# RAM_SDR_BGA54.net
KiCad netlist of a schematic drawn in Altium Designer
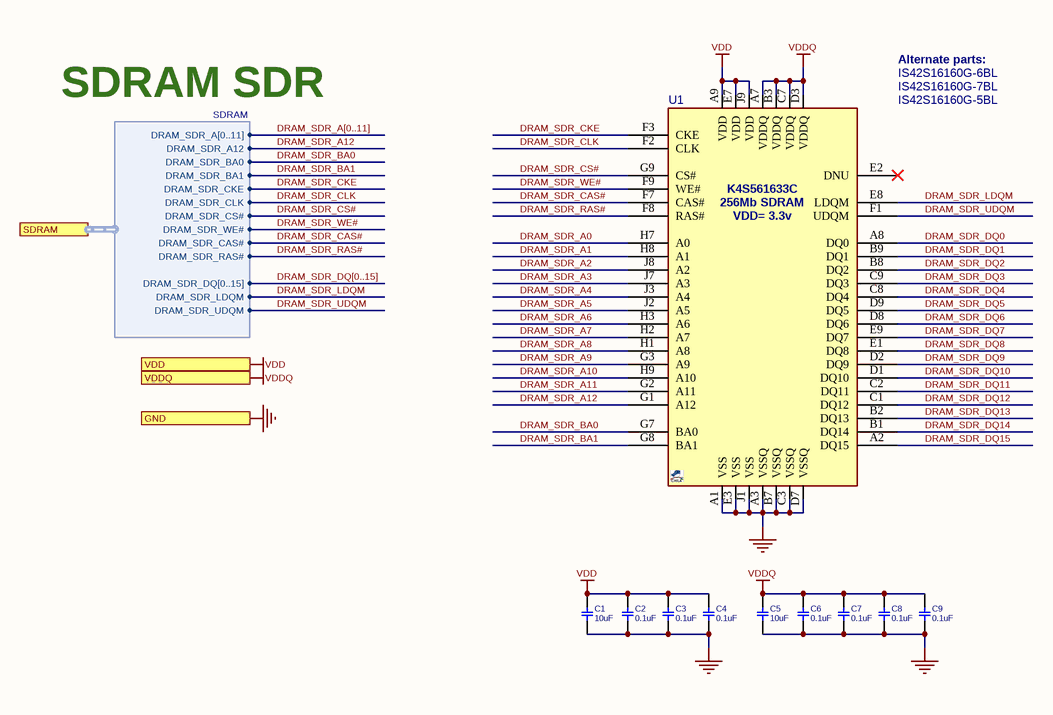
[diagram p0: RAM_SDR_BGA54.SchDoc]

(export (version "E")
  (design (tool "Eeschema 10.0.6"))
  (components
    (comp (ref "C1")
      (value "10uF")
      (footprint "C0402A")
      (description "CAP, MLCC")
      (fields (field (name "MANF_P#") "CL05A106MP5NUNC") (field (name "MANF") "Samsung"))
      (libsource (lib "passive_smd") (part "CAP_SMD_MLCC"))
    )
    (comp (ref "C2")
      (value "0.1uF")
      (footprint "C0402A")
      (description "CAP, MLCC")
      (fields (field (name "MANF_P#") "GRM155R61E104") (field (name "MANF") "Murata"))
      (libsource (lib "passive_smd") (part "CAP_SMD_MLCC"))
    )
    (comp (ref "C3")
      (value "0.1uF")
      (footprint "C0402A")
      (description "CAP, MLCC")
      (fields (field (name "MANF_P#") "GRM155R61E104") (field (name "MANF") "Murata"))
      (libsource (lib "passive_smd") (part "CAP_SMD_MLCC"))
    )
    (comp (ref "C4")
      (value "0.1uF")
      (footprint "C0402A")
      (description "CAP, MLCC")
      (fields (field (name "MANF_P#") "GRM155R61E104") (field (name "MANF") "Murata"))
      (libsource (lib "passive_smd") (part "CAP_SMD_MLCC"))
    )
    (comp (ref "C5")
      (value "10uF")
      (footprint "C0402A")
      (description "CAP, MLCC")
      (fields (field (name "MANF_P#") "CL05A106MP5NUNC") (field (name "MANF") "Samsung"))
      (libsource (lib "passive_smd") (part "CAP_SMD_MLCC"))
    )
    (comp (ref "C6")
      (value "0.1uF")
      (footprint "C0402A")
      (description "CAP, MLCC")
      (fields (field (name "MANF_P#") "GRM155R61E104") (field (name "MANF") "Murata"))
      (libsource (lib "passive_smd") (part "CAP_SMD_MLCC"))
    )
    (comp (ref "C7")
      (value "0.1uF")
      (footprint "C0402A")
      (description "CAP, MLCC")
      (fields (field (name "MANF_P#") "GRM155R61E104") (field (name "MANF") "Murata"))
      (libsource (lib "passive_smd") (part "CAP_SMD_MLCC"))
    )
    (comp (ref "C8")
      (value "0.1uF")
      (footprint "C0402A")
      (description "CAP, MLCC")
      (fields (field (name "MANF_P#") "GRM155R61E104") (field (name "MANF") "Murata"))
      (libsource (lib "passive_smd") (part "CAP_SMD_MLCC"))
    )
    (comp (ref "C9")
      (value "0.1uF")
      (footprint "C0402A")
      (description "CAP, MLCC")
      (fields (field (name "MANF_P#") "GRM155R61E104") (field (name "MANF") "Murata"))
      (libsource (lib "passive_smd") (part "CAP_SMD_MLCC"))
    )
    (comp (ref "U1")
      (value "K4S561633C")
      (footprint "BGA80_54_8X8")
      (description "SDRAM, 256Mb(4MbX16bX4), BGA-54")
      (fields (field (name "MANF") "ISSI") (field (name "MANF_P#") "K4S561633C-RL75"))
      (libsource (lib "memory_sdram") (part "SDRAM_K4S561633C_BGA54"))
    )
  )
  (nets
    (net (code "2") (name "/DRAM_SDR_A0") (class "Default")
      (node (ref "U1") (pin "H7") (pinfunction "A0_H7") (pintype "passive"))
    )
    (net (code "3") (name "/DRAM_SDR_A1") (class "Default")
      (node (ref "U1") (pin "H8") (pinfunction "A1_H8") (pintype "passive"))
    )
    (net (code "4") (name "/DRAM_SDR_A2") (class "Default")
      (node (ref "U1") (pin "J8") (pinfunction "A2_J8") (pintype "passive"))
    )
    (net (code "5") (name "/DRAM_SDR_A3") (class "Default")
      (node (ref "U1") (pin "J7") (pinfunction "A3_J7") (pintype "passive"))
    )
    (net (code "6") (name "/DRAM_SDR_A4") (class "Default")
      (node (ref "U1") (pin "J3") (pinfunction "A4_J3") (pintype "passive"))
    )
    (net (code "7") (name "/DRAM_SDR_A5") (class "Default")
      (node (ref "U1") (pin "J2") (pinfunction "A5_J2") (pintype "passive"))
    )
    (net (code "8") (name "/DRAM_SDR_A6") (class "Default")
      (node (ref "U1") (pin "H3") (pinfunction "A6_H3") (pintype "passive"))
    )
    (net (code "9") (name "/DRAM_SDR_A7") (class "Default")
      (node (ref "U1") (pin "H2") (pinfunction "A7_H2") (pintype "passive"))
    )
    (net (code "10") (name "/DRAM_SDR_A8") (class "Default")
      (node (ref "U1") (pin "H1") (pinfunction "A8_H1") (pintype "passive"))
    )
    (net (code "11") (name "/DRAM_SDR_A9") (class "Default")
      (node (ref "U1") (pin "G3") (pinfunction "A9_G3") (pintype "passive"))
    )
    (net (code "12") (name "/DRAM_SDR_A10") (class "Default")
      (node (ref "U1") (pin "H9") (pinfunction "A10_H9") (pintype "passive"))
    )
    (net (code "13") (name "/DRAM_SDR_A11") (class "Default")
      (node (ref "U1") (pin "G2") (pinfunction "A11_G2") (pintype "passive"))
    )
    (net (code "14") (name "/DRAM_SDR_A12") (class "Default")
      (node (ref "U1") (pin "G1") (pinfunction "A12_G1") (pintype "passive"))
    )
    (net (code "16") (name "/DRAM_SDR_BA0") (class "Default")
      (node (ref "U1") (pin "G7") (pinfunction "BA0_G7") (pintype "passive"))
    )
    (net (code "17") (name "/DRAM_SDR_BA1") (class "Default")
      (node (ref "U1") (pin "G8") (pinfunction "BA1_G8") (pintype "passive"))
    )
    (net (code "18") (name "/DRAM_SDR_CAS#") (class "Default")
      (node (ref "U1") (pin "F7") (pinfunction "CAS#_F7") (pintype "passive"))
    )
    (net (code "19") (name "/DRAM_SDR_CKE") (class "Default")
      (node (ref "U1") (pin "F3") (pinfunction "CKE_F3") (pintype "passive"))
    )
    (net (code "20") (name "/DRAM_SDR_CLK") (class "Default")
      (node (ref "U1") (pin "F2") (pinfunction "CLK_F2") (pintype "passive"))
    )
    (net (code "21") (name "/DRAM_SDR_CS#") (class "Default")
      (node (ref "U1") (pin "G9") (pinfunction "CS#_G9") (pintype "passive"))
    )
    (net (code "22") (name "/DRAM_SDR_DQ0") (class "Default")
      (node (ref "U1") (pin "A8") (pinfunction "DQ0_A8") (pintype "passive"))
    )
    (net (code "23") (name "/DRAM_SDR_DQ1") (class "Default")
      (node (ref "U1") (pin "B9") (pinfunction "DQ1_B9") (pintype "passive"))
    )
    (net (code "24") (name "/DRAM_SDR_DQ2") (class "Default")
      (node (ref "U1") (pin "B8") (pinfunction "DQ2_B8") (pintype "passive"))
    )
    (net (code "25") (name "/DRAM_SDR_DQ3") (class "Default")
      (node (ref "U1") (pin "C9") (pinfunction "DQ3_C9") (pintype "passive"))
    )
    (net (code "26") (name "/DRAM_SDR_DQ4") (class "Default")
      (node (ref "U1") (pin "C8") (pinfunction "DQ4_C8") (pintype "passive"))
    )
    (net (code "27") (name "/DRAM_SDR_DQ5") (class "Default")
      (node (ref "U1") (pin "D9") (pinfunction "DQ5_D9") (pintype "passive"))
    )
    (net (code "28") (name "/DRAM_SDR_DQ6") (class "Default")
      (node (ref "U1") (pin "D8") (pinfunction "DQ6_D8") (pintype "passive"))
    )
    (net (code "29") (name "/DRAM_SDR_DQ7") (class "Default")
      (node (ref "U1") (pin "E9") (pinfunction "DQ7_E9") (pintype "passive"))
    )
    (net (code "30") (name "/DRAM_SDR_DQ8") (class "Default")
      (node (ref "U1") (pin "E1") (pinfunction "DQ8_E1") (pintype "passive"))
    )
    (net (code "31") (name "/DRAM_SDR_DQ9") (class "Default")
      (node (ref "U1") (pin "D2") (pinfunction "DQ9_D2") (pintype "passive"))
    )
    (net (code "32") (name "/DRAM_SDR_DQ10") (class "Default")
      (node (ref "U1") (pin "D1") (pinfunction "DQ10_D1") (pintype "passive"))
    )
    (net (code "33") (name "/DRAM_SDR_DQ11") (class "Default")
      (node (ref "U1") (pin "C2") (pinfunction "DQ11_C2") (pintype "passive"))
    )
    (net (code "34") (name "/DRAM_SDR_DQ12") (class "Default")
      (node (ref "U1") (pin "C1") (pinfunction "DQ12_C1") (pintype "passive"))
    )
    (net (code "35") (name "/DRAM_SDR_DQ13") (class "Default")
      (node (ref "U1") (pin "B2") (pinfunction "DQ13_B2") (pintype "passive"))
    )
    (net (code "36") (name "/DRAM_SDR_DQ14") (class "Default")
      (node (ref "U1") (pin "B1") (pinfunction "DQ14_B1") (pintype "passive"))
    )
    (net (code "37") (name "/DRAM_SDR_DQ15") (class "Default")
      (node (ref "U1") (pin "A2") (pinfunction "DQ15_A2") (pintype "passive"))
    )
    (net (code "39") (name "/DRAM_SDR_LDQM") (class "Default")
      (node (ref "U1") (pin "E8") (pinfunction "LDQM_E8") (pintype "passive"))
    )
    (net (code "40") (name "/DRAM_SDR_RAS#") (class "Default")
      (node (ref "U1") (pin "F8") (pinfunction "RAS#_F8") (pintype "passive"))
    )
    (net (code "41") (name "/DRAM_SDR_UDQM") (class "Default")
      (node (ref "U1") (pin "F1") (pinfunction "UDQM_F1") (pintype "passive"))
    )
    (net (code "42") (name "/DRAM_SDR_WE#") (class "Default")
      (node (ref "U1") (pin "F9") (pinfunction "WE#_F9") (pintype "passive"))
    )
    (net (code "44") (name "GND") (class "Default")
      (node (ref "C1") (pin "1") (pinfunction "1_1") (pintype "passive"))
      (node (ref "C2") (pin "1") (pinfunction "1_1") (pintype "passive"))
      (node (ref "C3") (pin "1") (pinfunction "1_1") (pintype "passive"))
      (node (ref "C4") (pin "1") (pinfunction "1_1") (pintype "passive"))
      (node (ref "C5") (pin "1") (pinfunction "1_1") (pintype "passive"))
      (node (ref "C6") (pin "1") (pinfunction "1_1") (pintype "passive"))
      (node (ref "C7") (pin "1") (pinfunction "1_1") (pintype "passive"))
      (node (ref "C8") (pin "1") (pinfunction "1_1") (pintype "passive"))
      (node (ref "C9") (pin "1") (pinfunction "1_1") (pintype "passive"))
      (node (ref "U1") (pin "A1") (pinfunction "VSS_A1") (pintype "passive"))
      (node (ref "U1") (pin "A3") (pinfunction "VSSQ_A3") (pintype "passive"))
      (node (ref "U1") (pin "B7") (pinfunction "VSSQ_B7") (pintype "passive"))
      (node (ref "U1") (pin "C3") (pinfunction "VSSQ_C3") (pintype "passive"))
      (node (ref "U1") (pin "D7") (pinfunction "VSSQ_D7") (pintype "passive"))
      (node (ref "U1") (pin "E3") (pinfunction "VSS_E3") (pintype "passive"))
      (node (ref "U1") (pin "J1") (pinfunction "VSS_J1") (pintype "passive"))
    )
    (net (code "45") (name "VDD") (class "Default")
      (node (ref "C1") (pin "2") (pinfunction "2_2") (pintype "passive"))
      (node (ref "C2") (pin "2") (pinfunction "2_2") (pintype "passive"))
      (node (ref "C3") (pin "2") (pinfunction "2_2") (pintype "passive"))
      (node (ref "C4") (pin "2") (pinfunction "2_2") (pintype "passive"))
      (node (ref "U1") (pin "A9") (pinfunction "VDD_A9") (pintype "passive"))
      (node (ref "U1") (pin "E7") (pinfunction "VDD_E7") (pintype "passive"))
      (node (ref "U1") (pin "J9") (pinfunction "VDD_J9") (pintype "passive"))
    )
    (net (code "46") (name "VDDQ") (class "Default")
      (node (ref "C5") (pin "2") (pinfunction "2_2") (pintype "passive"))
      (node (ref "C6") (pin "2") (pinfunction "2_2") (pintype "passive"))
      (node (ref "C7") (pin "2") (pinfunction "2_2") (pintype "passive"))
      (node (ref "C8") (pin "2") (pinfunction "2_2") (pintype "passive"))
      (node (ref "C9") (pin "2") (pinfunction "2_2") (pintype "passive"))
      (node (ref "U1") (pin "A7") (pinfunction "VDDQ_A7") (pintype "passive"))
      (node (ref "U1") (pin "B3") (pinfunction "VDDQ_B3") (pintype "passive"))
      (node (ref "U1") (pin "C7") (pinfunction "VDDQ_C7") (pintype "passive"))
      (node (ref "U1") (pin "D3") (pinfunction "VDDQ_D3") (pintype "passive"))
    )
    (net (code "47") (name "unconnected-(U1-DNU-PadE2)") (class "Default")
      (node (ref "U1") (pin "E2") (pinfunction "DNU_E2") (pintype "passive+no_connect"))
    )
  )
)
